# untitled.net
KiCad netlist of a schematic drawn in EAGLE
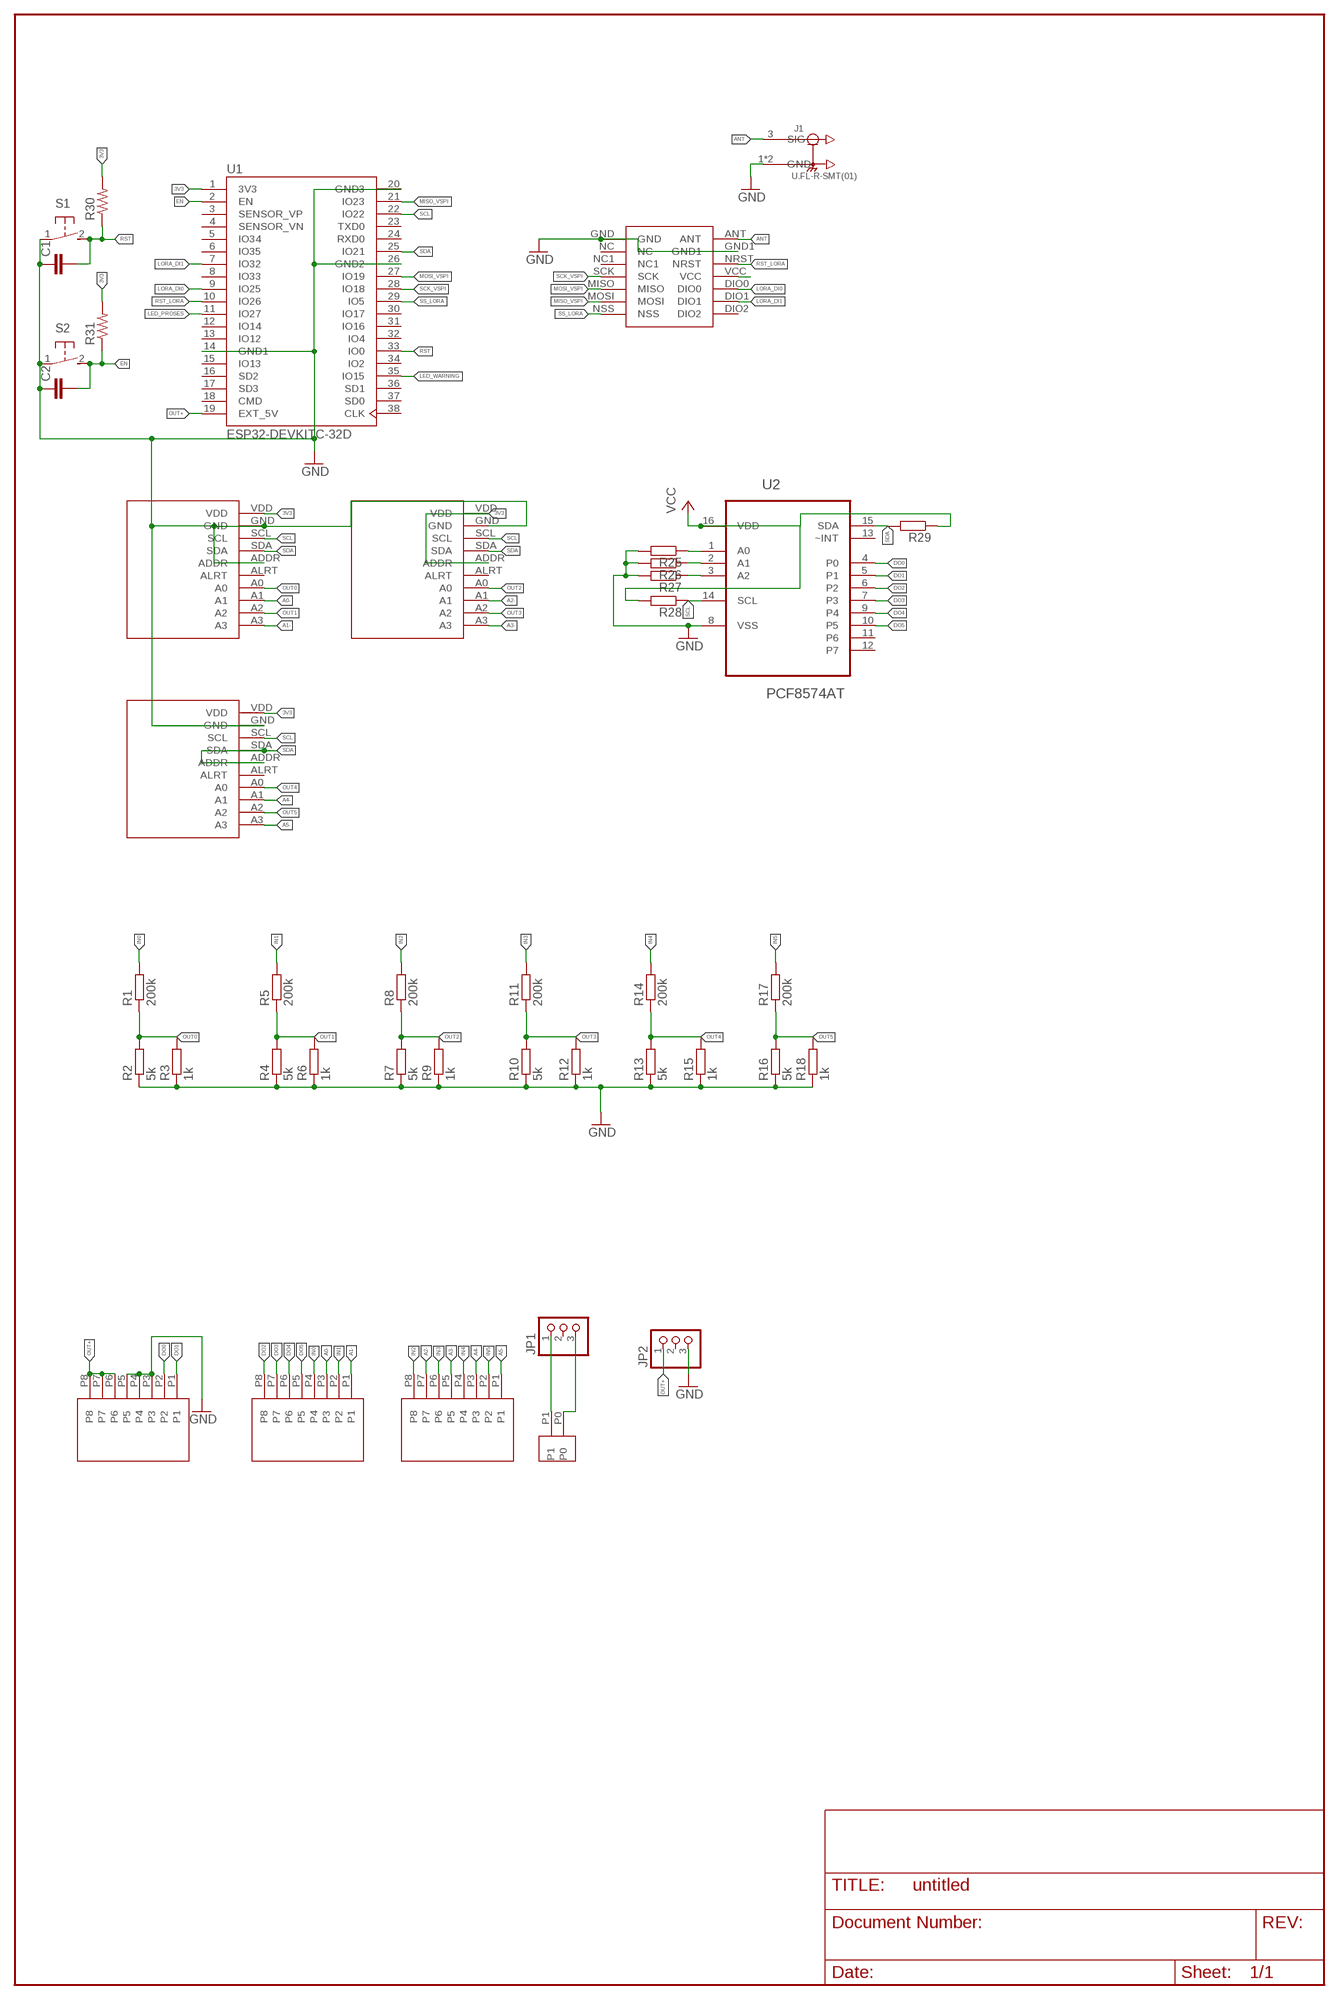
[diagram p0: schematic, sheet 1]

(export (version "E")
  (design (tool "Eeschema 10.0.6"))
  (components
    (comp (ref "ADS1")
      (value "ADS1115")
      (footprint "eagle-import:ADS1115")
      (libsource (lib "eagle-import") (part "ADS1115"))
    )
    (comp (ref "ADS2")
      (value "ADS1115")
      (footprint "eagle-import:ADS1115")
      (libsource (lib "eagle-import") (part "ADS1115"))
    )
    (comp (ref "ADS3")
      (value "ADS1115")
      (footprint "eagle-import:ADS1115")
      (libsource (lib "eagle-import") (part "ADS1115"))
    )
    (comp (ref "C1")
      (value "C-EUC0805K")
      (footprint "eagle-import:C0805K")
      (libsource (lib "eagle-import") (part "C-EUC0805K"))
    )
    (comp (ref "C2")
      (value "C-EUC0805K")
      (footprint "eagle-import:C0805K")
      (libsource (lib "eagle-import") (part "C-EUC0805K"))
    )
    (comp (ref "CONN2P-3.5PI1")
      (value "CONN2P-3.5PI")
      (footprint "eagle-import:CONN2P-3.5PI")
      (libsource (lib "eagle-import") (part "CONN2P-3.5PI"))
    )
    (comp (ref "CONN3.1")
      (value "CONN3.5")
      (footprint "eagle-import:CONN3.5")
      (libsource (lib "eagle-import") (part "CONN3.5"))
    )
    (comp (ref "CONN3.2")
      (value "CONN3.5")
      (footprint "eagle-import:CONN3.5")
      (libsource (lib "eagle-import") (part "CONN3.5"))
    )
    (comp (ref "CONN3.3")
      (value "CONN3.5")
      (footprint "eagle-import:CONN3.5")
      (libsource (lib "eagle-import") (part "CONN3.5"))
    )
    (comp (ref "J1")
      (value "U.FL-R-SMT(01)")
      (footprint "eagle-import:HRS_U.FL-R-SMT(01)")
      (fields (field (name "MF") "Hirose"))
      (libsource (lib "eagle-import") (part "U.FL-R-SMT(01)"))
    )
    (comp (ref "JP1")
      (value "PINHD-1X3")
      (footprint "eagle-import:1X03")
      (libsource (lib "eagle-import") (part "PINHD-1X3"))
    )
    (comp (ref "JP2")
      (value "PINHD-1X3")
      (footprint "eagle-import:1X03")
      (libsource (lib "eagle-import") (part "PINHD-1X3"))
    )
    (comp (ref "LORA-NICERF-V1")
      (value "LORA-NICERF-V2")
      (footprint "eagle-import:LORA-NICERF-V2")
      (libsource (lib "eagle-import") (part "LORA-NICERF-V2"))
    )
    (comp (ref "R1")
      (value "200k")
      (footprint "eagle-import:R0805")
      (libsource (lib "eagle-import") (part "R-EU_R0805"))
    )
    (comp (ref "R2")
      (value "5k")
      (footprint "eagle-import:R0805")
      (libsource (lib "eagle-import") (part "R-EU_R0805"))
    )
    (comp (ref "R3")
      (value "1k")
      (footprint "eagle-import:R0805")
      (libsource (lib "eagle-import") (part "R-EU_R0805"))
    )
    (comp (ref "R4")
      (value "5k")
      (footprint "eagle-import:R0805")
      (libsource (lib "eagle-import") (part "R-EU_R0805"))
    )
    (comp (ref "R5")
      (value "200k")
      (footprint "eagle-import:R0805")
      (libsource (lib "eagle-import") (part "R-EU_R0805"))
    )
    (comp (ref "R6")
      (value "1k")
      (footprint "eagle-import:R0805")
      (libsource (lib "eagle-import") (part "R-EU_R0805"))
    )
    (comp (ref "R7")
      (value "5k")
      (footprint "eagle-import:R0805")
      (libsource (lib "eagle-import") (part "R-EU_R0805"))
    )
    (comp (ref "R8")
      (value "200k")
      (footprint "eagle-import:R0805")
      (libsource (lib "eagle-import") (part "R-EU_R0805"))
    )
    (comp (ref "R9")
      (value "1k")
      (footprint "eagle-import:R0805")
      (libsource (lib "eagle-import") (part "R-EU_R0805"))
    )
    (comp (ref "R10")
      (value "5k")
      (footprint "eagle-import:R0805")
      (libsource (lib "eagle-import") (part "R-EU_R0805"))
    )
    (comp (ref "R11")
      (value "200k")
      (footprint "eagle-import:R0805")
      (libsource (lib "eagle-import") (part "R-EU_R0805"))
    )
    (comp (ref "R12")
      (value "1k")
      (footprint "eagle-import:R0805")
      (libsource (lib "eagle-import") (part "R-EU_R0805"))
    )
    (comp (ref "R13")
      (value "5k")
      (footprint "eagle-import:R0805")
      (libsource (lib "eagle-import") (part "R-EU_R0805"))
    )
    (comp (ref "R14")
      (value "200k")
      (footprint "eagle-import:R0805")
      (libsource (lib "eagle-import") (part "R-EU_R0805"))
    )
    (comp (ref "R15")
      (value "1k")
      (footprint "eagle-import:R0805")
      (libsource (lib "eagle-import") (part "R-EU_R0805"))
    )
    (comp (ref "R16")
      (value "5k")
      (footprint "eagle-import:R0805")
      (libsource (lib "eagle-import") (part "R-EU_R0805"))
    )
    (comp (ref "R17")
      (value "200k")
      (footprint "eagle-import:R0805")
      (libsource (lib "eagle-import") (part "R-EU_R0805"))
    )
    (comp (ref "R18")
      (value "1k")
      (footprint "eagle-import:R0805")
      (libsource (lib "eagle-import") (part "R-EU_R0805"))
    )
    (comp (ref "R25")
      (value "R-EU_R0805")
      (footprint "eagle-import:R0805")
      (libsource (lib "eagle-import") (part "R-EU_R0805"))
    )
    (comp (ref "R26")
      (value "R-EU_R0805")
      (footprint "eagle-import:R0805")
      (libsource (lib "eagle-import") (part "R-EU_R0805"))
    )
    (comp (ref "R27")
      (value "R-EU_R0805")
      (footprint "eagle-import:R0805")
      (libsource (lib "eagle-import") (part "R-EU_R0805"))
    )
    (comp (ref "R28")
      (value "R-EU_R0805")
      (footprint "eagle-import:R0805")
      (libsource (lib "eagle-import") (part "R-EU_R0805"))
    )
    (comp (ref "R29")
      (value "R-EU_R0805")
      (footprint "eagle-import:R0805")
      (libsource (lib "eagle-import") (part "R-EU_R0805"))
    )
    (comp (ref "R30")
      (value "R-US_M0805")
      (footprint "eagle-import:M0805")
      (libsource (lib "eagle-import") (part "R-US_M0805"))
    )
    (comp (ref "R31")
      (value "R-US_M0805")
      (footprint "eagle-import:M0805")
      (libsource (lib "eagle-import") (part "R-US_M0805"))
    )
    (comp (ref "S1")
      (value "31-XX")
      (footprint "eagle-import:B3F-31XX")
      (fields (field (name "MPN") "B3F-3100"))
      (libsource (lib "eagle-import") (part "31-XX"))
    )
    (comp (ref "S2")
      (value "31-XX")
      (footprint "eagle-import:B3F-31XX")
      (fields (field (name "MPN") "B3F-3100"))
      (libsource (lib "eagle-import") (part "31-XX"))
    )
    (comp (ref "U1")
      (value "ESP32-DEVKITC-32D")
      (footprint "eagle-import:MODULE_ESP32-DEVKITC-32D")
      (fields (field (name "MF") "Espressif Systems"))
      (libsource (lib "eagle-import") (part "ESP32-DEVKITC-32D"))
    )
    (comp (ref "U2")
      (value "PCF8574AT")
      (footprint "eagle-import:SOIC127P1032X265-16N")
      (fields (field (name "MF") "NXP USA"))
      (libsource (lib "eagle-import") (part "PCF8574AT"))
    )
  )
  (nets
    (net (code "1") (name "3V3") (class "Default")
      (node (ref "ADS1") (pin "VDD") (pinfunction "VDD_VDD") (pintype "bidirectional"))
      (node (ref "ADS2") (pin "ADDR") (pinfunction "ADDR_ADDR") (pintype "bidirectional"))
      (node (ref "ADS2") (pin "VDD") (pinfunction "VDD_VDD") (pintype "bidirectional"))
      (node (ref "ADS3") (pin "VDD") (pinfunction "VDD_VDD") (pintype "bidirectional"))
      (node (ref "R30") (pin "2") (pinfunction "2_2") (pintype "passive"))
      (node (ref "R31") (pin "2") (pinfunction "2_2") (pintype "passive"))
      (node (ref "U1") (pin "1") (pinfunction "3V3_1") (pintype "power_in"))
    )
    (net (code "2") (name "A0-") (class "Default")
      (node (ref "ADS1") (pin "A1") (pinfunction "A1_A1") (pintype "bidirectional"))
      (node (ref "CONN3.2") (pin "P3") (pinfunction "P3_P3") (pintype "bidirectional"))
    )
    (net (code "3") (name "A1-") (class "Default")
      (node (ref "ADS1") (pin "A3") (pinfunction "A3_A3") (pintype "bidirectional"))
      (node (ref "CONN3.2") (pin "P1") (pinfunction "P1_P1") (pintype "bidirectional"))
    )
    (net (code "4") (name "A2-") (class "Default")
      (node (ref "ADS2") (pin "A1") (pinfunction "A1_A1") (pintype "bidirectional"))
      (node (ref "CONN3.3") (pin "P7") (pinfunction "P7_P7") (pintype "bidirectional"))
    )
    (net (code "5") (name "A3-") (class "Default")
      (node (ref "ADS2") (pin "A3") (pinfunction "A3_A3") (pintype "bidirectional"))
      (node (ref "CONN3.3") (pin "P5") (pinfunction "P5_P5") (pintype "bidirectional"))
    )
    (net (code "6") (name "A4-") (class "Default")
      (node (ref "ADS3") (pin "A1") (pinfunction "A1_A1") (pintype "bidirectional"))
      (node (ref "CONN3.3") (pin "P3") (pinfunction "P3_P3") (pintype "bidirectional"))
    )
    (net (code "7") (name "A5-") (class "Default")
      (node (ref "ADS3") (pin "A3") (pinfunction "A3_A3") (pintype "bidirectional"))
      (node (ref "CONN3.3") (pin "P1") (pinfunction "P1_P1") (pintype "bidirectional"))
    )
    (net (code "8") (name "ANT") (class "Default")
      (node (ref "J1") (pin "3") (pinfunction "SIG_3") (pintype "passive"))
      (node (ref "LORA-NICERF-V1") (pin "ANT") (pinfunction "ANT_ANT") (pintype "bidirectional"))
    )
    (net (code "9") (name "DO0") (class "Default")
      (node (ref "CONN3.1") (pin "P2") (pinfunction "P2_P2") (pintype "bidirectional"))
      (node (ref "U2") (pin "4") (pinfunction "P0_4") (pintype "bidirectional"))
    )
    (net (code "10") (name "DO1") (class "Default")
      (node (ref "CONN3.1") (pin "P1") (pinfunction "P1_P1") (pintype "bidirectional"))
      (node (ref "U2") (pin "5") (pinfunction "P1_5") (pintype "bidirectional"))
    )
    (net (code "11") (name "DO2") (class "Default")
      (node (ref "CONN3.2") (pin "P8") (pinfunction "P8_P8") (pintype "bidirectional"))
      (node (ref "U2") (pin "6") (pinfunction "P2_6") (pintype "bidirectional"))
    )
    (net (code "12") (name "DO3") (class "Default")
      (node (ref "CONN3.2") (pin "P7") (pinfunction "P7_P7") (pintype "bidirectional"))
      (node (ref "U2") (pin "7") (pinfunction "P3_7") (pintype "bidirectional"))
    )
    (net (code "13") (name "DO4") (class "Default")
      (node (ref "CONN3.2") (pin "P6") (pinfunction "P6_P6") (pintype "bidirectional"))
      (node (ref "U2") (pin "9") (pinfunction "P4_9") (pintype "bidirectional"))
    )
    (net (code "14") (name "DO5") (class "Default")
      (node (ref "CONN3.2") (pin "P5") (pinfunction "P5_P5") (pintype "bidirectional"))
      (node (ref "U2") (pin "10") (pinfunction "P5_10") (pintype "bidirectional"))
    )
    (net (code "15") (name "EN") (class "Default")
      (node (ref "C2") (pin "2") (pinfunction "2_2") (pintype "passive"))
      (node (ref "R31") (pin "1") (pinfunction "1_1") (pintype "passive"))
      (node (ref "S2") (pin "2") (pinfunction "S_2") (pintype "passive"))
      (node (ref "U1") (pin "2") (pinfunction "EN_2") (pintype "input"))
    )
    (net (code "16") (name "GND") (class "Default")
      (node (ref "ADS1") (pin "ADDR") (pinfunction "ADDR_ADDR") (pintype "bidirectional"))
      (node (ref "ADS1") (pin "GND") (pinfunction "GND_GND") (pintype "bidirectional"))
      (node (ref "ADS2") (pin "GND") (pinfunction "GND_GND") (pintype "bidirectional"))
      (node (ref "ADS3") (pin "GND") (pinfunction "GND_GND") (pintype "bidirectional"))
      (node (ref "C1") (pin "1") (pinfunction "1_1") (pintype "passive"))
      (node (ref "C2") (pin "1") (pinfunction "1_1") (pintype "passive"))
      (node (ref "CONN3.1") (pin "P3") (pinfunction "P3_P3") (pintype "bidirectional"))
      (node (ref "CONN3.1") (pin "P4") (pinfunction "P4_P4") (pintype "bidirectional"))
      (node (ref "CONN3.1") (pin "P5") (pinfunction "P5_P5") (pintype "bidirectional"))
      (node (ref "J1") (pin "1") (pinfunction "GND_1") (pintype "passive"))
      (node (ref "J1") (pin "2") (pinfunction "GND_2") (pintype "passive"))
      (node (ref "JP2") (pin "3") (pinfunction "3_3") (pintype "passive"))
      (node (ref "LORA-NICERF-V1") (pin "GND") (pinfunction "GND_GND") (pintype "bidirectional"))
      (node (ref "LORA-NICERF-V1") (pin "GND1") (pinfunction "GND1_GND1") (pintype "bidirectional"))
      (node (ref "R10") (pin "1") (pinfunction "1_1") (pintype "passive"))
      (node (ref "R12") (pin "1") (pinfunction "1_1") (pintype "passive"))
      (node (ref "R13") (pin "1") (pinfunction "1_1") (pintype "passive"))
      (node (ref "R15") (pin "1") (pinfunction "1_1") (pintype "passive"))
      (node (ref "R16") (pin "1") (pinfunction "1_1") (pintype "passive"))
      (node (ref "R18") (pin "1") (pinfunction "1_1") (pintype "passive"))
      (node (ref "R2") (pin "1") (pinfunction "1_1") (pintype "passive"))
      (node (ref "R25") (pin "2") (pinfunction "2_2") (pintype "passive"))
      (node (ref "R26") (pin "2") (pinfunction "2_2") (pintype "passive"))
      (node (ref "R27") (pin "2") (pinfunction "2_2") (pintype "passive"))
      (node (ref "R3") (pin "1") (pinfunction "1_1") (pintype "passive"))
      (node (ref "R4") (pin "1") (pinfunction "1_1") (pintype "passive"))
      (node (ref "R6") (pin "1") (pinfunction "1_1") (pintype "passive"))
      (node (ref "R7") (pin "1") (pinfunction "1_1") (pintype "passive"))
      (node (ref "R9") (pin "1") (pinfunction "1_1") (pintype "passive"))
      (node (ref "S1") (pin "1") (pinfunction "P_1") (pintype "passive"))
      (node (ref "S2") (pin "1") (pinfunction "P_1") (pintype "passive"))
      (node (ref "U1") (pin "14") (pinfunction "GND1_14") (pintype "power_in"))
      (node (ref "U1") (pin "20") (pinfunction "GND3_20") (pintype "power_in"))
      (node (ref "U1") (pin "26") (pinfunction "GND2_26") (pintype "power_in"))
      (node (ref "U2") (pin "8") (pinfunction "VSS_8") (pintype "passive"))
    )
    (net (code "17") (name "IN0") (class "Default")
      (node (ref "CONN3.2") (pin "P4") (pinfunction "P4_P4") (pintype "bidirectional"))
      (node (ref "R1") (pin "2") (pinfunction "2_2") (pintype "passive"))
    )
    (net (code "18") (name "IN1") (class "Default")
      (node (ref "CONN3.2") (pin "P2") (pinfunction "P2_P2") (pintype "bidirectional"))
      (node (ref "R5") (pin "2") (pinfunction "2_2") (pintype "passive"))
    )
    (net (code "19") (name "IN2") (class "Default")
      (node (ref "CONN3.3") (pin "P8") (pinfunction "P8_P8") (pintype "bidirectional"))
      (node (ref "R8") (pin "2") (pinfunction "2_2") (pintype "passive"))
    )
    (net (code "20") (name "IN3") (class "Default")
      (node (ref "CONN3.3") (pin "P6") (pinfunction "P6_P6") (pintype "bidirectional"))
      (node (ref "R11") (pin "2") (pinfunction "2_2") (pintype "passive"))
    )
    (net (code "21") (name "IN4") (class "Default")
      (node (ref "CONN3.3") (pin "P4") (pinfunction "P4_P4") (pintype "bidirectional"))
      (node (ref "R14") (pin "2") (pinfunction "2_2") (pintype "passive"))
    )
    (net (code "22") (name "IN5") (class "Default")
      (node (ref "CONN3.3") (pin "P2") (pinfunction "P2_P2") (pintype "bidirectional"))
      (node (ref "R17") (pin "2") (pinfunction "2_2") (pintype "passive"))
    )
    (net (code "23") (name "LED_PROSES") (class "Default")
      (node (ref "U1") (pin "11") (pinfunction "IO27_11") (pintype "bidirectional"))
    )
    (net (code "24") (name "LED_WARNING") (class "Default")
      (node (ref "U1") (pin "35") (pinfunction "IO15_35") (pintype "bidirectional"))
    )
    (net (code "25") (name "LORA_DI0") (class "Default")
      (node (ref "LORA-NICERF-V1") (pin "DIO0") (pinfunction "DIO0_DIO0") (pintype "bidirectional"))
      (node (ref "U1") (pin "9") (pinfunction "IO25_9") (pintype "bidirectional"))
    )
    (net (code "26") (name "LORA_DI1") (class "Default")
      (node (ref "LORA-NICERF-V1") (pin "DIO1") (pinfunction "DIO1_DIO1") (pintype "bidirectional"))
      (node (ref "U1") (pin "7") (pinfunction "IO32_7") (pintype "bidirectional"))
    )
    (net (code "27") (name "MISO_VSPI") (class "Default")
      (node (ref "LORA-NICERF-V1") (pin "MOSI") (pinfunction "MOSI_MOSI") (pintype "bidirectional"))
      (node (ref "U1") (pin "21") (pinfunction "IO23_21") (pintype "bidirectional"))
    )
    (net (code "28") (name "MOSI_VSPI") (class "Default")
      (node (ref "LORA-NICERF-V1") (pin "MISO") (pinfunction "MISO_MISO") (pintype "bidirectional"))
      (node (ref "U1") (pin "27") (pinfunction "IO19_27") (pintype "bidirectional"))
    )
    (net (code "29") (name "Net-(CONN2P-3.5PI1-PadP0)") (class "Default")
      (node (ref "CONN2P-3.5PI1") (pin "P0") (pinfunction "P0_P0") (pintype "bidirectional"))
      (node (ref "JP1") (pin "3") (pinfunction "3_3") (pintype "passive"))
    )
    (net (code "30") (name "Net-(CONN2P-3.5PI1-PadP1)") (class "Default")
      (node (ref "CONN2P-3.5PI1") (pin "P1") (pinfunction "P1_P1") (pintype "bidirectional"))
      (node (ref "JP1") (pin "1") (pinfunction "1_1") (pintype "passive"))
    )
    (net (code "31") (name "Net-(U2-A0)") (class "Default")
      (node (ref "R25") (pin "1") (pinfunction "1_1") (pintype "passive"))
      (node (ref "U2") (pin "1") (pinfunction "A0_1") (pintype "input"))
    )
    (net (code "32") (name "Net-(U2-A1)") (class "Default")
      (node (ref "R26") (pin "1") (pinfunction "1_1") (pintype "passive"))
      (node (ref "U2") (pin "2") (pinfunction "A1_2") (pintype "input"))
    )
    (net (code "33") (name "Net-(U2-A2)") (class "Default")
      (node (ref "R27") (pin "1") (pinfunction "1_1") (pintype "passive"))
      (node (ref "U2") (pin "3") (pinfunction "A2_3") (pintype "input"))
    )
    (net (code "34") (name "OUT+") (class "Default")
      (node (ref "CONN3.1") (pin "P6") (pinfunction "P6_P6") (pintype "bidirectional"))
      (node (ref "CONN3.1") (pin "P7") (pinfunction "P7_P7") (pintype "bidirectional"))
      (node (ref "CONN3.1") (pin "P8") (pinfunction "P8_P8") (pintype "bidirectional"))
      (node (ref "JP2") (pin "1") (pinfunction "1_1") (pintype "passive"))
      (node (ref "U1") (pin "19") (pinfunction "EXT_5V_19") (pintype "power_in"))
    )
    (net (code "35") (name "OUT0") (class "Default")
      (node (ref "ADS1") (pin "A0") (pinfunction "A0_A0") (pintype "bidirectional"))
      (node (ref "R1") (pin "1") (pinfunction "1_1") (pintype "passive"))
      (node (ref "R2") (pin "2") (pinfunction "2_2") (pintype "passive"))
      (node (ref "R3") (pin "2") (pinfunction "2_2") (pintype "passive"))
    )
    (net (code "36") (name "OUT1") (class "Default")
      (node (ref "ADS1") (pin "A2") (pinfunction "A2_A2") (pintype "bidirectional"))
      (node (ref "R4") (pin "2") (pinfunction "2_2") (pintype "passive"))
      (node (ref "R5") (pin "1") (pinfunction "1_1") (pintype "passive"))
      (node (ref "R6") (pin "2") (pinfunction "2_2") (pintype "passive"))
    )
    (net (code "37") (name "OUT2") (class "Default")
      (node (ref "ADS2") (pin "A0") (pinfunction "A0_A0") (pintype "bidirectional"))
      (node (ref "R7") (pin "2") (pinfunction "2_2") (pintype "passive"))
      (node (ref "R8") (pin "1") (pinfunction "1_1") (pintype "passive"))
      (node (ref "R9") (pin "2") (pinfunction "2_2") (pintype "passive"))
    )
    (net (code "38") (name "OUT3") (class "Default")
      (node (ref "ADS2") (pin "A2") (pinfunction "A2_A2") (pintype "bidirectional"))
      (node (ref "R10") (pin "2") (pinfunction "2_2") (pintype "passive"))
      (node (ref "R11") (pin "1") (pinfunction "1_1") (pintype "passive"))
      (node (ref "R12") (pin "2") (pinfunction "2_2") (pintype "passive"))
    )
    (net (code "39") (name "OUT4") (class "Default")
      (node (ref "ADS3") (pin "A0") (pinfunction "A0_A0") (pintype "bidirectional"))
      (node (ref "R13") (pin "2") (pinfunction "2_2") (pintype "passive"))
      (node (ref "R14") (pin "1") (pinfunction "1_1") (pintype "passive"))
      (node (ref "R15") (pin "2") (pinfunction "2_2") (pintype "passive"))
    )
    (net (code "40") (name "OUT5") (class "Default")
      (node (ref "ADS3") (pin "A2") (pinfunction "A2_A2") (pintype "bidirectional"))
      (node (ref "R16") (pin "2") (pinfunction "2_2") (pintype "passive"))
      (node (ref "R17") (pin "1") (pinfunction "1_1") (pintype "passive"))
      (node (ref "R18") (pin "2") (pinfunction "2_2") (pintype "passive"))
    )
    (net (code "41") (name "RST") (class "Default")
      (node (ref "C1") (pin "2") (pinfunction "2_2") (pintype "passive"))
      (node (ref "R30") (pin "1") (pinfunction "1_1") (pintype "passive"))
      (node (ref "S1") (pin "2") (pinfunction "S_2") (pintype "passive"))
      (node (ref "U1") (pin "33") (pinfunction "IO0_33") (pintype "bidirectional"))
    )
    (net (code "42") (name "RST_LORA") (class "Default")
      (node (ref "LORA-NICERF-V1") (pin "NRST") (pinfunction "NRST_NRST") (pintype "bidirectional"))
      (node (ref "U1") (pin "10") (pinfunction "IO26_10") (pintype "bidirectional"))
    )
    (net (code "43") (name "SCK_VSPI") (class "Default")
      (node (ref "LORA-NICERF-V1") (pin "SCK") (pinfunction "SCK_SCK") (pintype "bidirectional"))
      (node (ref "U1") (pin "28") (pinfunction "IO18_28") (pintype "bidirectional"))
    )
    (net (code "44") (name "SCL") (class "Default")
      (node (ref "ADS1") (pin "SCL") (pinfunction "SCL_SCL") (pintype "bidirectional"))
      (node (ref "ADS2") (pin "SCL") (pinfunction "SCL_SCL") (pintype "bidirectional"))
      (node (ref "ADS3") (pin "SCL") (pinfunction "SCL_SCL") (pintype "bidirectional"))
      (node (ref "R28") (pin "1") (pinfunction "1_1") (pintype "passive"))
      (node (ref "U1") (pin "22") (pinfunction "IO22_22") (pintype "bidirectional"))
      (node (ref "U2") (pin "14") (pinfunction "SCL_14") (pintype "input"))
    )
    (net (code "45") (name "SDA") (class "Default")
      (node (ref "ADS1") (pin "SDA") (pinfunction "SDA_SDA") (pintype "bidirectional"))
      (node (ref "ADS2") (pin "SDA") (pinfunction "SDA_SDA") (pintype "bidirectional"))
      (node (ref "ADS3") (pin "ADDR") (pinfunction "ADDR_ADDR") (pintype "bidirectional"))
      (node (ref "ADS3") (pin "SDA") (pinfunction "SDA_SDA") (pintype "bidirectional"))
      (node (ref "R29") (pin "2") (pinfunction "2_2") (pintype "passive"))
      (node (ref "U1") (pin "25") (pinfunction "IO21_25") (pintype "bidirectional"))
      (node (ref "U2") (pin "15") (pinfunction "SDA_15") (pintype "bidirectional"))
    )
    (net (code "46") (name "SS_LORA") (class "Default")
      (node (ref "LORA-NICERF-V1") (pin "NSS") (pinfunction "NSS_NSS") (pintype "bidirectional"))
      (node (ref "U1") (pin "29") (pinfunction "IO5_29") (pintype "bidirectional"))
    )
    (net (code "47") (name "VCC") (class "Default")
      (node (ref "R28") (pin "2") (pinfunction "2_2") (pintype "passive"))
      (node (ref "R29") (pin "1") (pinfunction "1_1") (pintype "passive"))
      (node (ref "U2") (pin "16") (pinfunction "VDD_16") (pintype "power_in"))
    )
    (net (code "48") (name "unconnected-(ADS1-PadALRT)") (class "Default")
      (node (ref "ADS1") (pin "ALRT") (pinfunction "ALRT_ALRT") (pintype "bidirectional"))
    )
    (net (code "49") (name "unconnected-(ADS2-PadALRT)") (class "Default")
      (node (ref "ADS2") (pin "ALRT") (pinfunction "ALRT_ALRT") (pintype "bidirectional"))
    )
    (net (code "50") (name "unconnected-(ADS3-PadALRT)") (class "Default")
      (node (ref "ADS3") (pin "ALRT") (pinfunction "ALRT_ALRT") (pintype "bidirectional"))
    )
    (net (code "51") (name "unconnected-(JP1-Pad2)") (class "Default")
      (node (ref "JP1") (pin "2") (pinfunction "2_2") (pintype "passive"))
    )
    (net (code "52") (name "unconnected-(JP2-Pad2)") (class "Default")
      (node (ref "JP2") (pin "2") (pinfunction "2_2") (pintype "passive"))
    )
    (net (code "53") (name "unconnected-(LORA-NICERF-V1-PadDIO2)") (class "Default")
      (node (ref "LORA-NICERF-V1") (pin "DIO2") (pinfunction "DIO2_DIO2") (pintype "bidirectional"))
    )
    (net (code "54") (name "unconnected-(LORA-NICERF-V1-PadNC)") (class "Default")
      (node (ref "LORA-NICERF-V1") (pin "NC") (pinfunction "NC_NC") (pintype "bidirectional"))
    )
    (net (code "55") (name "unconnected-(LORA-NICERF-V1-PadNC1)") (class "Default")
      (node (ref "LORA-NICERF-V1") (pin "NC1") (pinfunction "NC1_NC1") (pintype "bidirectional"))
    )
    (net (code "56") (name "unconnected-(LORA-NICERF-V1-PadVCC)") (class "Default")
      (node (ref "LORA-NICERF-V1") (pin "VCC") (pinfunction "VCC_VCC") (pintype "bidirectional"))
    )
    (net (code "57") (name "unconnected-(U1-CLK-Pad38)") (class "Default")
      (node (ref "U1") (pin "38") (pinfunction "CLK_38") (pintype "input"))
    )
    (net (code "58") (name "unconnected-(U1-CMD-Pad18)") (class "Default")
      (node (ref "U1") (pin "18") (pinfunction "CMD_18") (pintype "bidirectional"))
    )
    (net (code "59") (name "unconnected-(U1-IO2-Pad34)") (class "Default")
      (node (ref "U1") (pin "34") (pinfunction "IO2_34") (pintype "bidirectional"))
    )
    (net (code "60") (name "unconnected-(U1-IO4-Pad32)") (class "Default")
      (node (ref "U1") (pin "32") (pinfunction "IO4_32") (pintype "bidirectional"))
    )
    (net (code "61") (name "unconnected-(U1-IO12-Pad13)") (class "Default")
      (node (ref "U1") (pin "13") (pinfunction "IO12_13") (pintype "bidirectional"))
    )
    (net (code "62") (name "unconnected-(U1-IO13-Pad15)") (class "Default")
      (node (ref "U1") (pin "15") (pinfunction "IO13_15") (pintype "bidirectional"))
    )
    (net (code "63") (name "unconnected-(U1-IO14-Pad12)") (class "Default")
      (node (ref "U1") (pin "12") (pinfunction "IO14_12") (pintype "bidirectional"))
    )
    (net (code "64") (name "unconnected-(U1-IO16-Pad31)") (class "Default")
      (node (ref "U1") (pin "31") (pinfunction "IO16_31") (pintype "bidirectional"))
    )
    (net (code "65") (name "unconnected-(U1-IO17-Pad30)") (class "Default")
      (node (ref "U1") (pin "30") (pinfunction "IO17_30") (pintype "bidirectional"))
    )
    (net (code "66") (name "unconnected-(U1-IO33-Pad8)") (class "Default")
      (node (ref "U1") (pin "8") (pinfunction "IO33_8") (pintype "bidirectional"))
    )
    (net (code "67") (name "unconnected-(U1-IO34-Pad5)") (class "Default")
      (node (ref "U1") (pin "5") (pinfunction "IO34_5") (pintype "bidirectional"))
    )
    (net (code "68") (name "unconnected-(U1-IO35-Pad6)") (class "Default")
      (node (ref "U1") (pin "6") (pinfunction "IO35_6") (pintype "bidirectional"))
    )
    (net (code "69") (name "unconnected-(U1-RXD0-Pad24)") (class "Default")
      (node (ref "U1") (pin "24") (pinfunction "RXD0_24") (pintype "input"))
    )
    (net (code "70") (name "unconnected-(U1-SD0-Pad37)") (class "Default")
      (node (ref "U1") (pin "37") (pinfunction "SD0_37") (pintype "bidirectional"))
    )
    (net (code "71") (name "unconnected-(U1-SD1-Pad36)") (class "Default")
      (node (ref "U1") (pin "36") (pinfunction "SD1_36") (pintype "bidirectional"))
    )
    (net (code "72") (name "unconnected-(U1-SD2-Pad16)") (class "Default")
      (node (ref "U1") (pin "16") (pinfunction "SD2_16") (pintype "bidirectional"))
    )
    (net (code "73") (name "unconnected-(U1-SD3-Pad17)") (class "Default")
      (node (ref "U1") (pin "17") (pinfunction "SD3_17") (pintype "bidirectional"))
    )
    (net (code "74") (name "unconnected-(U1-SENSOR_VN-Pad4)") (class "Default")
      (node (ref "U1") (pin "4") (pinfunction "SENSOR_VN_4") (pintype "input"))
    )
    (net (code "75") (name "unconnected-(U1-SENSOR_VP-Pad3)") (class "Default")
      (node (ref "U1") (pin "3") (pinfunction "SENSOR_VP_3") (pintype "input"))
    )
    (net (code "76") (name "unconnected-(U1-TXD0-Pad23)") (class "Default")
      (node (ref "U1") (pin "23") (pinfunction "TXD0_23") (pintype "output"))
    )
    (net (code "77") (name "unconnected-(U2-P6-Pad11)") (class "Default")
      (node (ref "U2") (pin "11") (pinfunction "P6_11") (pintype "bidirectional"))
    )
    (net (code "78") (name "unconnected-(U2-P7-Pad12)") (class "Default")
      (node (ref "U2") (pin "12") (pinfunction "P7_12") (pintype "bidirectional"))
    )
    (net (code "79") (name "unconnected-(U2-~{INT}-Pad13)") (class "Default")
      (node (ref "U2") (pin "13") (pinfunction "~{INT}_13") (pintype "output"))
    )
  )
)
